# 08_FPGA_banks_1_2_3_4.net
KiCad netlist of a schematic drawn in Altium Designer
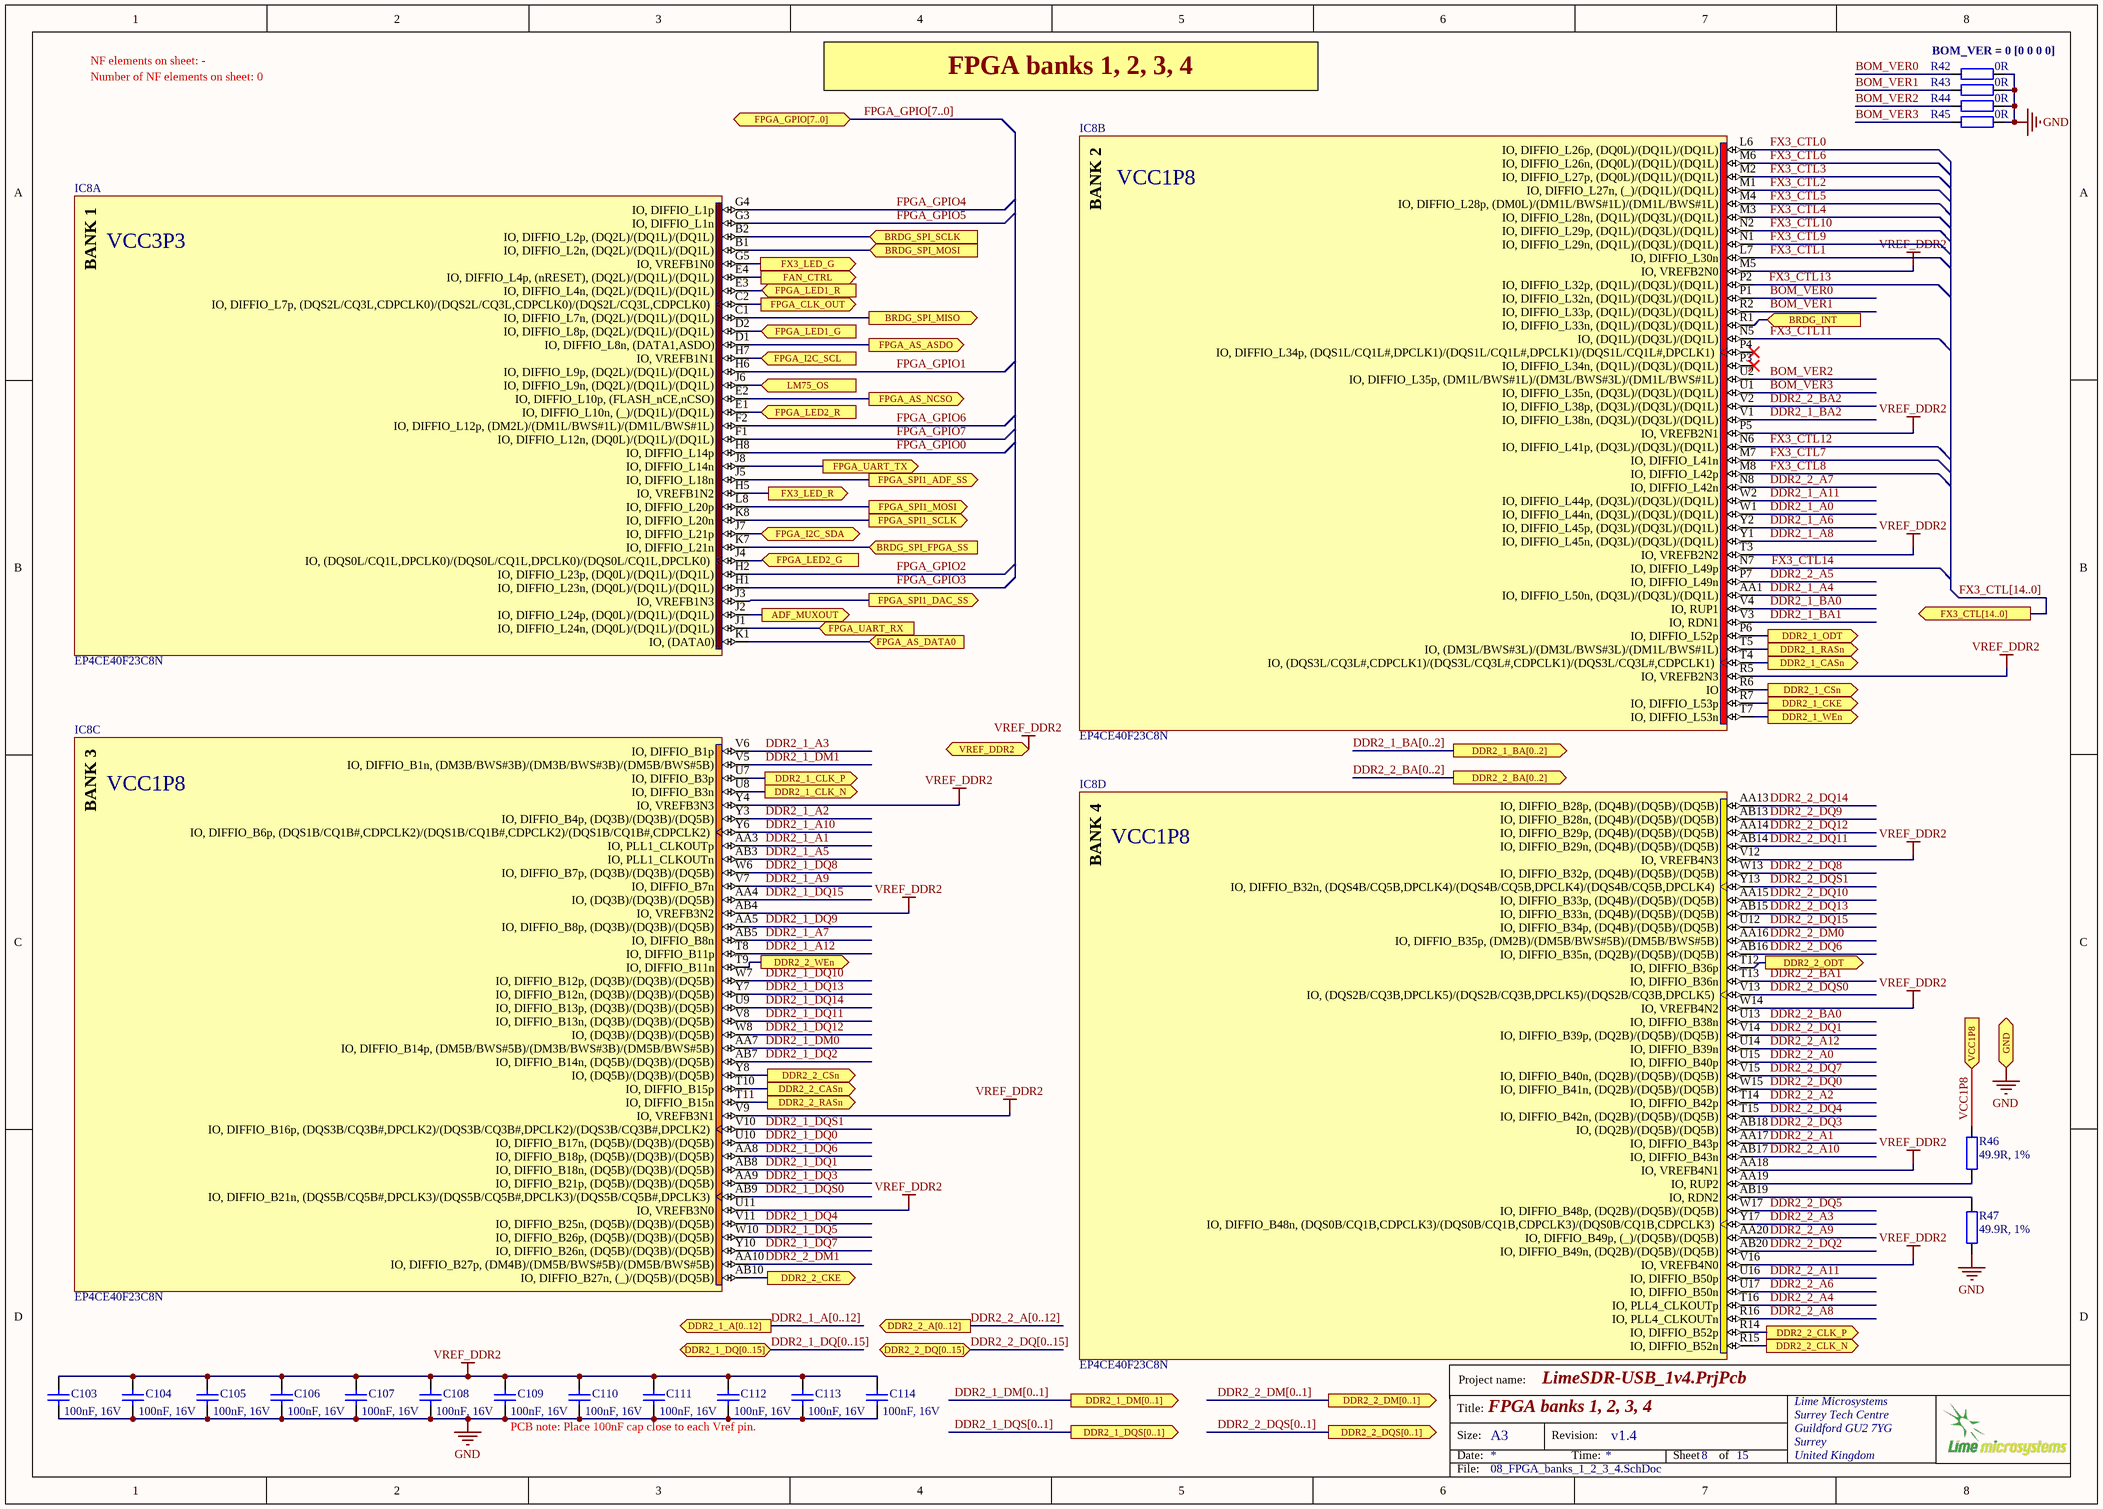
[diagram p0: 08_FPGA_banks_1_2_3_4.SchDoc]

(export (version "E")
  (design (tool "Eeschema 10.0.6"))
  (components
    (comp (ref "C103")
      (value "100nF, 16V")
      (footprint "CAP0402")
      (fields
        (field (name "TOLERANCE") "10 %")
        (field (name "MANUFACTURER") "Murata Electronics")
        (field (name "MANUFACTURER PART NUMBER") "GRM155R71C104KA88D")
      )
      (libsource (lib "LimeFPGAboard_schLib") (part "Cap_0603"))
    )
    (comp (ref "C104")
      (value "100nF, 16V")
      (footprint "CAP0402")
      (fields
        (field (name "TOLERANCE") "10 %")
        (field (name "MANUFACTURER") "Murata Electronics")
        (field (name "MANUFACTURER PART NUMBER") "GRM155R71C104KA88D")
      )
      (libsource (lib "LimeFPGAboard_schLib") (part "Cap_0603"))
    )
    (comp (ref "C105")
      (value "100nF, 16V")
      (footprint "CAP0402")
      (fields
        (field (name "TOLERANCE") "10 %")
        (field (name "MANUFACTURER") "Murata Electronics")
        (field (name "MANUFACTURER PART NUMBER") "GRM155R71C104KA88D")
      )
      (libsource (lib "LimeFPGAboard_schLib") (part "Cap_0603"))
    )
    (comp (ref "C106")
      (value "100nF, 16V")
      (footprint "CAP0402")
      (fields
        (field (name "TOLERANCE") "10 %")
        (field (name "MANUFACTURER") "Murata Electronics")
        (field (name "MANUFACTURER PART NUMBER") "GRM155R71C104KA88D")
      )
      (libsource (lib "LimeFPGAboard_schLib") (part "Cap_0603"))
    )
    (comp (ref "C107")
      (value "100nF, 16V")
      (footprint "CAP0402")
      (fields
        (field (name "TOLERANCE") "10 %")
        (field (name "MANUFACTURER") "Murata Electronics")
        (field (name "MANUFACTURER PART NUMBER") "GRM155R71C104KA88D")
      )
      (libsource (lib "LimeFPGAboard_schLib") (part "Cap_0603"))
    )
    (comp (ref "C108")
      (value "100nF, 16V")
      (footprint "CAP0402")
      (fields
        (field (name "TOLERANCE") "10 %")
        (field (name "MANUFACTURER") "Murata Electronics")
        (field (name "MANUFACTURER PART NUMBER") "GRM155R71C104KA88D")
      )
      (libsource (lib "LimeFPGAboard_schLib") (part "Cap_0603"))
    )
    (comp (ref "C109")
      (value "100nF, 16V")
      (footprint "CAP0402")
      (fields
        (field (name "TOLERANCE") "10 %")
        (field (name "MANUFACTURER") "Murata Electronics")
        (field (name "MANUFACTURER PART NUMBER") "GRM155R71C104KA88D")
      )
      (libsource (lib "LimeFPGAboard_schLib") (part "Cap_0603"))
    )
    (comp (ref "C110")
      (value "100nF, 16V")
      (footprint "CAP0402")
      (fields
        (field (name "TOLERANCE") "10 %")
        (field (name "MANUFACTURER") "Murata Electronics")
        (field (name "MANUFACTURER PART NUMBER") "GRM155R71C104KA88D")
      )
      (libsource (lib "LimeFPGAboard_schLib") (part "Cap_0603"))
    )
    (comp (ref "C111")
      (value "100nF, 16V")
      (footprint "CAP0402")
      (fields
        (field (name "TOLERANCE") "10 %")
        (field (name "MANUFACTURER") "Murata Electronics")
        (field (name "MANUFACTURER PART NUMBER") "GRM155R71C104KA88D")
      )
      (libsource (lib "LimeFPGAboard_schLib") (part "Cap_0603"))
    )
    (comp (ref "C112")
      (value "100nF, 16V")
      (footprint "CAP0402")
      (fields
        (field (name "TOLERANCE") "10 %")
        (field (name "MANUFACTURER") "Murata Electronics")
        (field (name "MANUFACTURER PART NUMBER") "GRM155R71C104KA88D")
      )
      (libsource (lib "LimeFPGAboard_schLib") (part "Cap_0603"))
    )
    (comp (ref "C113")
      (value "100nF, 16V")
      (footprint "CAP0402")
      (fields
        (field (name "TOLERANCE") "10 %")
        (field (name "MANUFACTURER") "Murata Electronics")
        (field (name "MANUFACTURER PART NUMBER") "GRM155R71C104KA88D")
      )
      (libsource (lib "LimeFPGAboard_schLib") (part "Cap_0603"))
    )
    (comp (ref "C114")
      (value "100nF, 16V")
      (footprint "CAP0402")
      (fields
        (field (name "TOLERANCE") "10 %")
        (field (name "MANUFACTURER") "Murata Electronics")
        (field (name "MANUFACTURER PART NUMBER") "GRM155R71C104KA88D")
      )
      (libsource (lib "LimeFPGAboard_schLib") (part "Cap_0603"))
    )
    (comp (ref "IC8")
      (value "EP4CE40F23C8N")
      (footprint "FBGA484_A-240")
      (description "IC FPGA 328 I/O 484FBGA")
      (fields (field (name "MANUFACTURER") "Altera"))
      (libsource (lib "LimeMicroAltiumLib_schLib") (part "EP4CE40F23C7N"))
    )
    (comp (ref "R42")
      (value "0R")
      (footprint "RES0402")
      (fields (field (name "MANUFACTURER") "Yageo"))
      (libsource (lib "LimeFPGAboard_schLib") (part "Res_0402"))
    )
    (comp (ref "R43")
      (value "0R")
      (footprint "RES0402")
      (fields (field (name "MANUFACTURER") "Yageo"))
      (libsource (lib "LimeFPGAboard_schLib") (part "Res_0402"))
    )
    (comp (ref "R44")
      (value "0R")
      (footprint "RES0402")
      (fields (field (name "MANUFACTURER") "Yageo"))
      (libsource (lib "LimeFPGAboard_schLib") (part "Res_0402"))
    )
    (comp (ref "R45")
      (value "0R")
      (footprint "RES0402")
      (fields (field (name "MANUFACTURER") "Yageo"))
      (libsource (lib "LimeFPGAboard_schLib") (part "Res_0402"))
    )
    (comp (ref "R46")
      (value "49.9R, 1%")
      (footprint "RES0402")
      (fields
        (field (name "TOLERANCE") "±1%")
        (field (name "MANUFACTURER") "Samsung Electro-Mechanics America, Inc.")
        (field (name "MANUFACTURER PART NUMBER") "RC1005F49R9CS")
      )
      (libsource (lib "LimeMicroAltiumLib_schLib") (part "Res_0402"))
    )
    (comp (ref "R47")
      (value "49.9R, 1%")
      (footprint "RES0402")
      (fields
        (field (name "TOLERANCE") "±1%")
        (field (name "MANUFACTURER") "Samsung Electro-Mechanics America, Inc.")
        (field (name "MANUFACTURER PART NUMBER") "RC1005F49R9CS")
      )
      (libsource (lib "LimeMicroAltiumLib_schLib") (part "Res_0402"))
    )
  )
  (nets
    (net (code "1") (name "/ADF_MUXOUT") (class "Default")
      (node (ref "IC8") (pin "J2") (pinfunction "IO,_DIFFIO_L24p,_(DQ0L)/(DQ1L)/(DQ1L)_J2") (pintype "bidirectional"))
    )
    (net (code "2") (name "/BOM_VER0") (class "Default")
      (node (ref "IC8") (pin "P1") (pinfunction "IO,_DIFFIO_L32n,_(DQ1L)/(DQ3L)/(DQ1L)_P1") (pintype "bidirectional"))
      (node (ref "R42") (pin "1") (pinfunction "1_1") (pintype "passive"))
    )
    (net (code "3") (name "/BOM_VER1") (class "Default")
      (node (ref "IC8") (pin "R2") (pinfunction "IO,_DIFFIO_L33p,_(DQ1L)/(DQ3L)/(DQ1L)_R2") (pintype "bidirectional"))
      (node (ref "R43") (pin "1") (pinfunction "1_1") (pintype "passive"))
    )
    (net (code "4") (name "/BOM_VER2") (class "Default")
      (node (ref "IC8") (pin "U2") (pinfunction "IO,_DIFFIO_L35p,_(DM1L/BWS#1L)/(DM3L/BWS#3L)/(DM1L/BWS#1L)_U2") (pintype "bidirectional"))
      (node (ref "R44") (pin "1") (pinfunction "1_1") (pintype "passive"))
    )
    (net (code "5") (name "/BOM_VER3") (class "Default")
      (node (ref "IC8") (pin "U1") (pinfunction "IO,_DIFFIO_L35n,_(DQ3L)/(DQ3L)/(DQ1L)_U1") (pintype "bidirectional"))
      (node (ref "R45") (pin "1") (pinfunction "1_1") (pintype "passive"))
    )
    (net (code "6") (name "/BRDG_INT") (class "Default")
      (node (ref "IC8") (pin "R1") (pinfunction "IO,_DIFFIO_L33n,_(DQ1L)/(DQ3L)/(DQ1L)_R1") (pintype "bidirectional"))
    )
    (net (code "7") (name "/BRDG_SPI_FPGA_SS") (class "Default")
      (node (ref "IC8") (pin "K7") (pinfunction "IO,_DIFFIO_L21n_K7") (pintype "bidirectional"))
    )
    (net (code "8") (name "/BRDG_SPI_MISO") (class "Default")
      (node (ref "IC8") (pin "C1") (pinfunction "IO,_DIFFIO_L7n,_(DQ2L)/(DQ1L)/(DQ1L)_C1") (pintype "bidirectional"))
    )
    (net (code "9") (name "/BRDG_SPI_MOSI") (class "Default")
      (node (ref "IC8") (pin "B1") (pinfunction "IO,_DIFFIO_L2n,_(DQ2L)/(DQ1L)/(DQ1L)_B1") (pintype "bidirectional"))
    )
    (net (code "10") (name "/BRDG_SPI_SCLK") (class "Default")
      (node (ref "IC8") (pin "B2") (pinfunction "IO,_DIFFIO_L2p,_(DQ2L)/(DQ1L)/(DQ1L)_B2") (pintype "bidirectional"))
    )
    (net (code "11") (name "/DDR2_1_A0") (class "Default")
      (node (ref "IC8") (pin "W1") (pinfunction "IO,_DIFFIO_L44n,_(DQ3L)/(DQ3L)/(DQ1L)_W1") (pintype "bidirectional"))
    )
    (net (code "12") (name "/DDR2_1_A1") (class "Default")
      (node (ref "IC8") (pin "AA3") (pinfunction "IO,_PLL1_CLKOUTp_AA3") (pintype "bidirectional"))
    )
    (net (code "13") (name "/DDR2_1_A2") (class "Default")
      (node (ref "IC8") (pin "Y3") (pinfunction "IO,_DIFFIO_B4p,_(DQ3B)/(DQ3B)/(DQ5B)_Y3") (pintype "bidirectional"))
    )
    (net (code "14") (name "/DDR2_1_A3") (class "Default")
      (node (ref "IC8") (pin "V6") (pinfunction "IO,_DIFFIO_B1p_V6") (pintype "bidirectional"))
    )
    (net (code "15") (name "/DDR2_1_A4") (class "Default")
      (node (ref "IC8") (pin "AA1") (pinfunction "IO,_DIFFIO_L50n,_(DQ3L)/(DQ3L)/(DQ1L)_AA1") (pintype "bidirectional"))
    )
    (net (code "16") (name "/DDR2_1_A5") (class "Default")
      (node (ref "IC8") (pin "AB3") (pinfunction "IO,_PLL1_CLKOUTn_AB3") (pintype "bidirectional"))
    )
    (net (code "17") (name "/DDR2_1_A6") (class "Default")
      (node (ref "IC8") (pin "Y2") (pinfunction "IO,_DIFFIO_L45p,_(DQ3L)/(DQ3L)/(DQ1L)_Y2") (pintype "bidirectional"))
    )
    (net (code "18") (name "/DDR2_1_A7") (class "Default")
      (node (ref "IC8") (pin "AB5") (pinfunction "IO,_DIFFIO_B8n_AB5") (pintype "bidirectional"))
    )
    (net (code "19") (name "/DDR2_1_A8") (class "Default")
      (node (ref "IC8") (pin "Y1") (pinfunction "IO,_DIFFIO_L45n,_(DQ3L)/(DQ3L)/(DQ1L)_Y1") (pintype "bidirectional"))
    )
    (net (code "20") (name "/DDR2_1_A9") (class "Default")
      (node (ref "IC8") (pin "V7") (pinfunction "IO,_DIFFIO_B7n_V7") (pintype "bidirectional"))
    )
    (net (code "21") (name "/DDR2_1_A10") (class "Default")
      (node (ref "IC8") (pin "Y6") (pinfunction "IO,_DIFFIO_B6p,_(DQS1B/CQ1B#,CDPCLK2)/(DQS1B/CQ1B#,CDPCLK2)/(DQS1B/CQ1B#,CDPCLK2)_Y6") (pintype "bidirectional"))
    )
    (net (code "22") (name "/DDR2_1_A11") (class "Default")
      (node (ref "IC8") (pin "W2") (pinfunction "IO,_DIFFIO_L44p,_(DQ3L)/(DQ3L)/(DQ1L)_W2") (pintype "bidirectional"))
    )
    (net (code "23") (name "/DDR2_1_A12") (class "Default")
      (node (ref "IC8") (pin "T8") (pinfunction "IO,_DIFFIO_B11p_T8") (pintype "bidirectional"))
    )
    (net (code "25") (name "/DDR2_1_BA0") (class "Default")
      (node (ref "IC8") (pin "V4") (pinfunction "IO,_RUP1_V4") (pintype "bidirectional"))
    )
    (net (code "26") (name "/DDR2_1_BA1") (class "Default")
      (node (ref "IC8") (pin "V3") (pinfunction "IO,_RDN1_V3") (pintype "bidirectional"))
    )
    (net (code "27") (name "/DDR2_1_BA2") (class "Default")
      (node (ref "IC8") (pin "V1") (pinfunction "IO,_DIFFIO_L38n,_(DQ3L)/(DQ3L)/(DQ1L)_V1") (pintype "bidirectional"))
    )
    (net (code "29") (name "/DDR2_1_CASn") (class "Default")
      (node (ref "IC8") (pin "T4") (pinfunction "IO,_(DQS3L/CQ3L#,CDPCLK1)/(DQS3L/CQ3L#,CDPCLK1)/(DQS3L/CQ3L#,CDPCLK1)_T4") (pintype "bidirectional"))
    )
    (net (code "30") (name "/DDR2_1_CKE") (class "Default")
      (node (ref "IC8") (pin "R7") (pinfunction "IO,_DIFFIO_L53p_R7") (pintype "bidirectional"))
    )
    (net (code "31") (name "/DDR2_1_CLK_N") (class "Default")
      (node (ref "IC8") (pin "U8") (pinfunction "IO,_DIFFIO_B3n_U8") (pintype "bidirectional"))
    )
    (net (code "32") (name "/DDR2_1_CLK_P") (class "Default")
      (node (ref "IC8") (pin "U7") (pinfunction "IO,_DIFFIO_B3p_U7") (pintype "bidirectional"))
    )
    (net (code "33") (name "/DDR2_1_CSn") (class "Default")
      (node (ref "IC8") (pin "R6") (pinfunction "IO_R6") (pintype "bidirectional"))
    )
    (net (code "34") (name "/DDR2_1_DM0") (class "Default")
      (node (ref "IC8") (pin "AA7") (pinfunction "IO,_DIFFIO_B14p,_(DM5B/BWS#5B)/(DM3B/BWS#3B)/(DM5B/BWS#5B)_AA7") (pintype "bidirectional"))
    )
    (net (code "35") (name "/DDR2_1_DM1") (class "Default")
      (node (ref "IC8") (pin "V5") (pinfunction "IO,_DIFFIO_B1n,_(DM3B/BWS#3B)/(DM3B/BWS#3B)/(DM5B/BWS#5B)_V5") (pintype "bidirectional"))
    )
    (net (code "37") (name "/DDR2_1_DQ0") (class "Default")
      (node (ref "IC8") (pin "U10") (pinfunction "IO,_DIFFIO_B17n,_(DQ5B)/(DQ3B)/(DQ5B)_U10") (pintype "bidirectional"))
    )
    (net (code "38") (name "/DDR2_1_DQ1") (class "Default")
      (node (ref "IC8") (pin "AB8") (pinfunction "IO,_DIFFIO_B18n,_(DQ5B)/(DQ3B)/(DQ5B)_AB8") (pintype "bidirectional"))
    )
    (net (code "39") (name "/DDR2_1_DQ2") (class "Default")
      (node (ref "IC8") (pin "AB7") (pinfunction "IO,_DIFFIO_B14n,_(DQ5B)/(DQ3B)/(DQ5B)_AB7") (pintype "bidirectional"))
    )
    (net (code "40") (name "/DDR2_1_DQ3") (class "Default")
      (node (ref "IC8") (pin "AA9") (pinfunction "IO,_DIFFIO_B21p,_(DQ5B)/(DQ3B)/(DQ5B)_AA9") (pintype "bidirectional"))
    )
    (net (code "41") (name "/DDR2_1_DQ4") (class "Default")
      (node (ref "IC8") (pin "V11") (pinfunction "IO,_DIFFIO_B25n,_(DQ5B)/(DQ3B)/(DQ5B)_V11") (pintype "bidirectional"))
    )
    (net (code "42") (name "/DDR2_1_DQ5") (class "Default")
      (node (ref "IC8") (pin "W10") (pinfunction "IO,_DIFFIO_B26p,_(DQ5B)/(DQ3B)/(DQ5B)_W10") (pintype "bidirectional"))
    )
    (net (code "43") (name "/DDR2_1_DQ6") (class "Default")
      (node (ref "IC8") (pin "AA8") (pinfunction "IO,_DIFFIO_B18p,_(DQ5B)/(DQ3B)/(DQ5B)_AA8") (pintype "bidirectional"))
    )
    (net (code "44") (name "/DDR2_1_DQ7") (class "Default")
      (node (ref "IC8") (pin "Y10") (pinfunction "IO,_DIFFIO_B26n,_(DQ5B)/(DQ3B)/(DQ5B)_Y10") (pintype "bidirectional"))
    )
    (net (code "45") (name "/DDR2_1_DQ8") (class "Default")
      (node (ref "IC8") (pin "W6") (pinfunction "IO,_DIFFIO_B7p,_(DQ3B)/(DQ3B)/(DQ5B)_W6") (pintype "bidirectional"))
    )
    (net (code "46") (name "/DDR2_1_DQ9") (class "Default")
      (node (ref "IC8") (pin "AA5") (pinfunction "IO,_DIFFIO_B8p,_(DQ3B)/(DQ3B)/(DQ5B)_AA5") (pintype "bidirectional"))
    )
    (net (code "47") (name "/DDR2_1_DQ10") (class "Default")
      (node (ref "IC8") (pin "W7") (pinfunction "IO,_DIFFIO_B12p,_(DQ3B)/(DQ3B)/(DQ5B)_W7") (pintype "bidirectional"))
    )
    (net (code "48") (name "/DDR2_1_DQ11") (class "Default")
      (node (ref "IC8") (pin "V8") (pinfunction "IO,_DIFFIO_B13n,_(DQ3B)/(DQ3B)/(DQ5B)_V8") (pintype "bidirectional"))
    )
    (net (code "49") (name "/DDR2_1_DQ12") (class "Default")
      (node (ref "IC8") (pin "W8") (pinfunction "IO,_(DQ3B)/(DQ3B)/(DQ5B)_W8") (pintype "bidirectional"))
    )
    (net (code "50") (name "/DDR2_1_DQ13") (class "Default")
      (node (ref "IC8") (pin "Y7") (pinfunction "IO,_DIFFIO_B12n,_(DQ3B)/(DQ3B)/(DQ5B)_Y7") (pintype "bidirectional"))
    )
    (net (code "51") (name "/DDR2_1_DQ14") (class "Default")
      (node (ref "IC8") (pin "U9") (pinfunction "IO,_DIFFIO_B13p,_(DQ3B)/(DQ3B)/(DQ5B)_U9") (pintype "bidirectional"))
    )
    (net (code "52") (name "/DDR2_1_DQ15") (class "Default")
      (node (ref "IC8") (pin "AA4") (pinfunction "IO,_(DQ3B)/(DQ3B)/(DQ5B)_AA4") (pintype "bidirectional"))
    )
    (net (code "53") (name "/DDR2_1_DQS0") (class "Default")
      (node (ref "IC8") (pin "AB9") (pinfunction "IO,_DIFFIO_B21n,_(DQS5B/CQ5B#,DPCLK3)/(DQS5B/CQ5B#,DPCLK3)/(DQS5B/CQ5B#,DPCLK3)_AB9") (pintype "bidirectional"))
    )
    (net (code "54") (name "/DDR2_1_DQS1") (class "Default")
      (node (ref "IC8") (pin "V10") (pinfunction "IO,_DIFFIO_B16p,_(DQS3B/CQ3B#,DPCLK2)/(DQS3B/CQ3B#,DPCLK2)/(DQS3B/CQ3B#,DPCLK2)_V10") (pintype "bidirectional"))
    )
    (net (code "57") (name "/DDR2_1_ODT") (class "Default")
      (node (ref "IC8") (pin "P6") (pinfunction "IO,_DIFFIO_L52p_P6") (pintype "bidirectional"))
    )
    (net (code "58") (name "/DDR2_1_RASn") (class "Default")
      (node (ref "IC8") (pin "T5") (pinfunction "IO,_(DM3L/BWS#3L)/(DM3L/BWS#3L)/(DM1L/BWS#1L)_T5") (pintype "bidirectional"))
    )
    (net (code "59") (name "/DDR2_1_WEn") (class "Default")
      (node (ref "IC8") (pin "T7") (pinfunction "IO,_DIFFIO_L53n_T7") (pintype "bidirectional"))
    )
    (net (code "60") (name "/DDR2_2_A0") (class "Default")
      (node (ref "IC8") (pin "U15") (pinfunction "IO,_DIFFIO_B40p_U15") (pintype "bidirectional"))
    )
    (net (code "61") (name "/DDR2_2_A1") (class "Default")
      (node (ref "IC8") (pin "AA17") (pinfunction "IO,_DIFFIO_B43p_AA17") (pintype "bidirectional"))
    )
    (net (code "62") (name "/DDR2_2_A2") (class "Default")
      (node (ref "IC8") (pin "T14") (pinfunction "IO,_DIFFIO_B42p_T14") (pintype "bidirectional"))
    )
    (net (code "63") (name "/DDR2_2_A3") (class "Default")
      (node (ref "IC8") (pin "Y17") (pinfunction "IO,_DIFFIO_B48n,_(DQS0B/CQ1B,CDPCLK3)/(DQS0B/CQ1B,CDPCLK3)/(DQS0B/CQ1B,CDPCLK3)_Y17") (pintype "bidirectional"))
    )
    (net (code "64") (name "/DDR2_2_A4") (class "Default")
      (node (ref "IC8") (pin "T16") (pinfunction "IO,_PLL4_CLKOUTp_T16") (pintype "bidirectional"))
    )
    (net (code "65") (name "/DDR2_2_A5") (class "Default")
      (node (ref "IC8") (pin "P7") (pinfunction "IO,_DIFFIO_L49n_P7") (pintype "bidirectional"))
    )
    (net (code "66") (name "/DDR2_2_A6") (class "Default")
      (node (ref "IC8") (pin "U17") (pinfunction "IO,_DIFFIO_B50n_U17") (pintype "bidirectional"))
    )
    (net (code "67") (name "/DDR2_2_A7") (class "Default")
      (node (ref "IC8") (pin "N8") (pinfunction "IO,_DIFFIO_L42n_N8") (pintype "bidirectional"))
    )
    (net (code "68") (name "/DDR2_2_A8") (class "Default")
      (node (ref "IC8") (pin "R16") (pinfunction "IO,_PLL4_CLKOUTn_R16") (pintype "bidirectional"))
    )
    (net (code "69") (name "/DDR2_2_A9") (class "Default")
      (node (ref "IC8") (pin "AA20") (pinfunction "IO,_DIFFIO_B49p,_(_)/(DQ5B)/(DQ5B)_AA20") (pintype "bidirectional"))
    )
    (net (code "70") (name "/DDR2_2_A10") (class "Default")
      (node (ref "IC8") (pin "AB17") (pinfunction "IO,_DIFFIO_B43n_AB17") (pintype "bidirectional"))
    )
    (net (code "71") (name "/DDR2_2_A11") (class "Default")
      (node (ref "IC8") (pin "U16") (pinfunction "IO,_DIFFIO_B50p_U16") (pintype "bidirectional"))
    )
    (net (code "72") (name "/DDR2_2_A12") (class "Default")
      (node (ref "IC8") (pin "U14") (pinfunction "IO,_DIFFIO_B39n_U14") (pintype "bidirectional"))
    )
    (net (code "74") (name "/DDR2_2_BA0") (class "Default")
      (node (ref "IC8") (pin "U13") (pinfunction "IO,_DIFFIO_B38n_U13") (pintype "bidirectional"))
    )
    (net (code "75") (name "/DDR2_2_BA1") (class "Default")
      (node (ref "IC8") (pin "T13") (pinfunction "IO,_DIFFIO_B36n_T13") (pintype "bidirectional"))
    )
    (net (code "76") (name "/DDR2_2_BA2") (class "Default")
      (node (ref "IC8") (pin "V2") (pinfunction "IO,_DIFFIO_L38p,_(DQ3L)/(DQ3L)/(DQ1L)_V2") (pintype "bidirectional"))
    )
    (net (code "78") (name "/DDR2_2_CASn") (class "Default")
      (node (ref "IC8") (pin "T10") (pinfunction "IO,_DIFFIO_B15p_T10") (pintype "bidirectional"))
    )
    (net (code "79") (name "/DDR2_2_CKE") (class "Default")
      (node (ref "IC8") (pin "AB10") (pinfunction "IO,_DIFFIO_B27n,_(_)/(DQ5B)/(DQ5B)_AB10") (pintype "bidirectional"))
    )
    (net (code "80") (name "/DDR2_2_CLK_N") (class "Default")
      (node (ref "IC8") (pin "R15") (pinfunction "IO,_DIFFIO_B52n_R15") (pintype "bidirectional"))
    )
    (net (code "81") (name "/DDR2_2_CLK_P") (class "Default")
      (node (ref "IC8") (pin "R14") (pinfunction "IO,_DIFFIO_B52p_R14") (pintype "bidirectional"))
    )
    (net (code "82") (name "/DDR2_2_CSn") (class "Default")
      (node (ref "IC8") (pin "Y8") (pinfunction "IO,_(DQ5B)/(DQ3B)/(DQ5B)_Y8") (pintype "bidirectional"))
    )
    (net (code "83") (name "/DDR2_2_DM0") (class "Default")
      (node (ref "IC8") (pin "AA16") (pinfunction "IO,_DIFFIO_B35p,_(DM2B)/(DM5B/BWS#5B)/(DM5B/BWS#5B)_AA16") (pintype "bidirectional"))
    )
    (net (code "84") (name "/DDR2_2_DM1") (class "Default")
      (node (ref "IC8") (pin "AA10") (pinfunction "IO,_DIFFIO_B27p,_(DM4B)/(DM5B/BWS#5B)/(DM5B/BWS#5B)_AA10") (pintype "bidirectional"))
    )
    (net (code "86") (name "/DDR2_2_DQ0") (class "Default")
      (node (ref "IC8") (pin "W15") (pinfunction "IO,_DIFFIO_B41n,_(DQ2B)/(DQ5B)/(DQ5B)_W15") (pintype "bidirectional"))
    )
    (net (code "87") (name "/DDR2_2_DQ1") (class "Default")
      (node (ref "IC8") (pin "V14") (pinfunction "IO,_DIFFIO_B39p,_(DQ2B)/(DQ5B)/(DQ5B)_V14") (pintype "bidirectional"))
    )
    (net (code "88") (name "/DDR2_2_DQ2") (class "Default")
      (node (ref "IC8") (pin "AB20") (pinfunction "IO,_DIFFIO_B49n,_(DQ2B)/(DQ5B)/(DQ5B)_AB20") (pintype "bidirectional"))
    )
    (net (code "89") (name "/DDR2_2_DQ3") (class "Default")
      (node (ref "IC8") (pin "AB18") (pinfunction "IO,_(DQ2B)/(DQ5B)/(DQ5B)_AB18") (pintype "bidirectional"))
    )
    (net (code "90") (name "/DDR2_2_DQ4") (class "Default")
      (node (ref "IC8") (pin "T15") (pinfunction "IO,_DIFFIO_B42n,_(DQ2B)/(DQ5B)/(DQ5B)_T15") (pintype "bidirectional"))
    )
    (net (code "91") (name "/DDR2_2_DQ5") (class "Default")
      (node (ref "IC8") (pin "W17") (pinfunction "IO,_DIFFIO_B48p,_(DQ2B)/(DQ5B)/(DQ5B)_W17") (pintype "bidirectional"))
    )
    (net (code "92") (name "/DDR2_2_DQ6") (class "Default")
      (node (ref "IC8") (pin "AB16") (pinfunction "IO,_DIFFIO_B35n,_(DQ2B)/(DQ5B)/(DQ5B)_AB16") (pintype "bidirectional"))
    )
    (net (code "93") (name "/DDR2_2_DQ7") (class "Default")
      (node (ref "IC8") (pin "V15") (pinfunction "IO,_DIFFIO_B40n,_(DQ2B)/(DQ5B)/(DQ5B)_V15") (pintype "bidirectional"))
    )
    (net (code "94") (name "/DDR2_2_DQ8") (class "Default")
      (node (ref "IC8") (pin "W13") (pinfunction "IO,_DIFFIO_B32p,_(DQ4B)/(DQ5B)/(DQ5B)_W13") (pintype "bidirectional"))
    )
    (net (code "95") (name "/DDR2_2_DQ9") (class "Default")
      (node (ref "IC8") (pin "AB13") (pinfunction "IO,_DIFFIO_B28n,_(DQ4B)/(DQ5B)/(DQ5B)_AB13") (pintype "bidirectional"))
    )
    (net (code "96") (name "/DDR2_2_DQ10") (class "Default")
      (node (ref "IC8") (pin "AA15") (pinfunction "IO,_DIFFIO_B33p,_(DQ4B)/(DQ5B)/(DQ5B)_AA15") (pintype "bidirectional"))
    )
    (net (code "97") (name "/DDR2_2_DQ11") (class "Default")
      (node (ref "IC8") (pin "AB14") (pinfunction "IO,_DIFFIO_B29n,_(DQ4B)/(DQ5B)/(DQ5B)_AB14") (pintype "bidirectional"))
    )
    (net (code "98") (name "/DDR2_2_DQ12") (class "Default")
      (node (ref "IC8") (pin "AA14") (pinfunction "IO,_DIFFIO_B29p,_(DQ4B)/(DQ5B)/(DQ5B)_AA14") (pintype "bidirectional"))
    )
    (net (code "99") (name "/DDR2_2_DQ13") (class "Default")
      (node (ref "IC8") (pin "AB15") (pinfunction "IO,_DIFFIO_B33n,_(DQ4B)/(DQ5B)/(DQ5B)_AB15") (pintype "bidirectional"))
    )
    (net (code "100") (name "/DDR2_2_DQ14") (class "Default")
      (node (ref "IC8") (pin "AA13") (pinfunction "IO,_DIFFIO_B28p,_(DQ4B)/(DQ5B)/(DQ5B)_AA13") (pintype "bidirectional"))
    )
    (net (code "101") (name "/DDR2_2_DQ15") (class "Default")
      (node (ref "IC8") (pin "U12") (pinfunction "IO,_DIFFIO_B34p,_(DQ4B)/(DQ5B)/(DQ5B)_U12") (pintype "bidirectional"))
    )
    (net (code "102") (name "/DDR2_2_DQS0") (class "Default")
      (node (ref "IC8") (pin "V13") (pinfunction "IO,_(DQS2B/CQ3B,DPCLK5)/(DQS2B/CQ3B,DPCLK5)/(DQS2B/CQ3B,DPCLK5)_V13") (pintype "bidirectional"))
    )
    (net (code "103") (name "/DDR2_2_DQS1") (class "Default")
      (node (ref "IC8") (pin "Y13") (pinfunction "IO,_DIFFIO_B32n,_(DQS4B/CQ5B,DPCLK4)/(DQS4B/CQ5B,DPCLK4)/(DQS4B/CQ5B,DPCLK4)_Y13") (pintype "bidirectional"))
    )
    (net (code "106") (name "/DDR2_2_ODT") (class "Default")
      (node (ref "IC8") (pin "T12") (pinfunction "IO,_DIFFIO_B36p_T12") (pintype "bidirectional"))
    )
    (net (code "107") (name "/DDR2_2_RASn") (class "Default")
      (node (ref "IC8") (pin "T11") (pinfunction "IO,_DIFFIO_B15n_T11") (pintype "bidirectional"))
    )
    (net (code "108") (name "/DDR2_2_WEn") (class "Default")
      (node (ref "IC8") (pin "T9") (pinfunction "IO,_DIFFIO_B11n_T9") (pintype "bidirectional"))
    )
    (net (code "109") (name "/FAN_CTRL") (class "Default")
      (node (ref "IC8") (pin "E4") (pinfunction "IO,_DIFFIO_L4p,_(nRESET),_(DQ2L)/(DQ1L)/(DQ1L)_E4") (pintype "bidirectional"))
    )
    (net (code "110") (name "/FPGA_AS_ASDO") (class "Default")
      (node (ref "IC8") (pin "D1") (pinfunction "IO,_DIFFIO_L8n,_(DATA1,ASDO)_D1") (pintype "bidirectional"))
    )
    (net (code "111") (name "/FPGA_AS_DATA0") (class "Default")
      (node (ref "IC8") (pin "K1") (pinfunction "IO,_(DATA0)_K1") (pintype "bidirectional"))
    )
    (net (code "112") (name "/FPGA_AS_NCSO") (class "Default")
      (node (ref "IC8") (pin "E2") (pinfunction "IO,_DIFFIO_L10p,_(FLASH_nCE,nCSO)_E2") (pintype "bidirectional"))
    )
    (net (code "113") (name "/FPGA_CLK_OUT") (class "Default")
      (node (ref "IC8") (pin "C2") (pinfunction "IO,_DIFFIO_L7p,_(DQS2L/CQ3L,CDPCLK0)/(DQS2L/CQ3L,CDPCLK0)/(DQS2L/CQ3L,CDPCLK0)_C2") (pintype "bidirectional"))
    )
    (net (code "114") (name "/FPGA_GPIO0") (class "Default")
      (node (ref "IC8") (pin "H8") (pinfunction "IO,_DIFFIO_L14p_H8") (pintype "bidirectional"))
    )
    (net (code "115") (name "/FPGA_GPIO1") (class "Default")
      (node (ref "IC8") (pin "H6") (pinfunction "IO,_DIFFIO_L9p,_(DQ2L)/(DQ1L)/(DQ1L)_H6") (pintype "bidirectional"))
    )
    (net (code "116") (name "/FPGA_GPIO2") (class "Default")
      (node (ref "IC8") (pin "H2") (pinfunction "IO,_DIFFIO_L23p,_(DQ0L)/(DQ1L)/(DQ1L)_H2") (pintype "bidirectional"))
    )
    (net (code "117") (name "/FPGA_GPIO3") (class "Default")
      (node (ref "IC8") (pin "H1") (pinfunction "IO,_DIFFIO_L23n,_(DQ0L)/(DQ1L)/(DQ1L)_H1") (pintype "bidirectional"))
    )
    (net (code "118") (name "/FPGA_GPIO4") (class "Default")
      (node (ref "IC8") (pin "G4") (pinfunction "IO,_DIFFIO_L1p_G4") (pintype "bidirectional"))
    )
    (net (code "119") (name "/FPGA_GPIO5") (class "Default")
      (node (ref "IC8") (pin "G3") (pinfunction "IO,_DIFFIO_L1n_G3") (pintype "bidirectional"))
    )
    (net (code "120") (name "/FPGA_GPIO6") (class "Default")
      (node (ref "IC8") (pin "F2") (pinfunction "IO,_DIFFIO_L12p,_(DM2L)/(DM1L/BWS#1L)/(DM1L/BWS#1L)_F2") (pintype "bidirectional"))
    )
    (net (code "121") (name "/FPGA_GPIO7") (class "Default")
      (node (ref "IC8") (pin "F1") (pinfunction "IO,_DIFFIO_L12n,_(DQ0L)/(DQ1L)/(DQ1L)_F1") (pintype "bidirectional"))
    )
    (net (code "123") (name "/FPGA_I2C_SCL") (class "Default")
      (node (ref "IC8") (pin "H7") (pinfunction "IO,_VREFB1N1_H7") (pintype "bidirectional"))
    )
    (net (code "124") (name "/FPGA_I2C_SDA") (class "Default")
      (node (ref "IC8") (pin "J7") (pinfunction "IO,_DIFFIO_L21p_J7") (pintype "bidirectional"))
    )
    (net (code "125") (name "/FPGA_LED1_G") (class "Default")
      (node (ref "IC8") (pin "D2") (pinfunction "IO,_DIFFIO_L8p,_(DQ2L)/(DQ1L)/(DQ1L)_D2") (pintype "bidirectional"))
    )
    (net (code "126") (name "/FPGA_LED1_R") (class "Default")
      (node (ref "IC8") (pin "E3") (pinfunction "IO,_DIFFIO_L4n,_(DQ2L)/(DQ1L)/(DQ1L)_E3") (pintype "bidirectional"))
    )
    (net (code "127") (name "/FPGA_LED2_G") (class "Default")
      (node (ref "IC8") (pin "J4") (pinfunction "IO,_(DQS0L/CQ1L,DPCLK0)/(DQS0L/CQ1L,DPCLK0)/(DQS0L/CQ1L,DPCLK0)_J4") (pintype "bidirectional"))
    )
    (net (code "128") (name "/FPGA_LED2_R") (class "Default")
      (node (ref "IC8") (pin "E1") (pinfunction "IO,_DIFFIO_L10n,_(_)/(DQ1L)/(DQ1L)_E1") (pintype "bidirectional"))
    )
    (net (code "129") (name "/FPGA_SPI1_ADF_SS") (class "Default")
      (node (ref "IC8") (pin "J5") (pinfunction "IO,_DIFFIO_L18n_J5") (pintype "bidirectional"))
    )
    (net (code "130") (name "/FPGA_SPI1_DAC_SS") (class "Default")
      (node (ref "IC8") (pin "J3") (pinfunction "IO,_VREFB1N3_J3") (pintype "bidirectional"))
    )
    (net (code "131") (name "/FPGA_SPI1_MOSI") (class "Default")
      (node (ref "IC8") (pin "L8") (pinfunction "IO,_DIFFIO_L20p_L8") (pintype "bidirectional"))
    )
    (net (code "132") (name "/FPGA_SPI1_SCLK") (class "Default")
      (node (ref "IC8") (pin "K8") (pinfunction "IO,_DIFFIO_L20n_K8") (pintype "bidirectional"))
    )
    (net (code "133") (name "/FPGA_UART_RX") (class "Default")
      (node (ref "IC8") (pin "J1") (pinfunction "IO,_DIFFIO_L24n,_(DQ0L)/(DQ1L)/(DQ1L)_J1") (pintype "bidirectional"))
    )
    (net (code "134") (name "/FPGA_UART_TX") (class "Default")
      (node (ref "IC8") (pin "J8") (pinfunction "IO,_DIFFIO_L14n_J8") (pintype "bidirectional"))
    )
    (net (code "135") (name "/FX3_CTL0") (class "Default")
      (node (ref "IC8") (pin "L6") (pinfunction "IO,_DIFFIO_L26p,_(DQ0L)/(DQ1L)/(DQ1L)_L6") (pintype "bidirectional"))
    )
    (net (code "136") (name "/FX3_CTL1") (class "Default")
      (node (ref "IC8") (pin "L7") (pinfunction "IO,_DIFFIO_L30n_L7") (pintype "bidirectional"))
    )
    (net (code "137") (name "/FX3_CTL2") (class "Default")
      (node (ref "IC8") (pin "M1") (pinfunction "IO,_DIFFIO_L27n,_(_)/(DQ1L)/(DQ1L)_M1") (pintype "bidirectional"))
    )
    (net (code "138") (name "/FX3_CTL3") (class "Default")
      (node (ref "IC8") (pin "M2") (pinfunction "IO,_DIFFIO_L27p,_(DQ0L)/(DQ1L)/(DQ1L)_M2") (pintype "bidirectional"))
    )
    (net (code "139") (name "/FX3_CTL4") (class "Default")
      (node (ref "IC8") (pin "M3") (pinfunction "IO,_DIFFIO_L28n,_(DQ1L)/(DQ3L)/(DQ1L)_M3") (pintype "bidirectional"))
    )
    (net (code "140") (name "/FX3_CTL5") (class "Default")
      (node (ref "IC8") (pin "M4") (pinfunction "IO,_DIFFIO_L28p,_(DM0L)/(DM1L/BWS#1L)/(DM1L/BWS#1L)_M4") (pintype "bidirectional"))
    )
    (net (code "141") (name "/FX3_CTL6") (class "Default")
      (node (ref "IC8") (pin "M6") (pinfunction "IO,_DIFFIO_L26n,_(DQ0L)/(DQ1L)/(DQ1L)_M6") (pintype "bidirectional"))
    )
    (net (code "142") (name "/FX3_CTL7") (class "Default")
      (node (ref "IC8") (pin "M7") (pinfunction "IO,_DIFFIO_L41n_M7") (pintype "bidirectional"))
    )
    (net (code "143") (name "/FX3_CTL8") (class "Default")
      (node (ref "IC8") (pin "M8") (pinfunction "IO,_DIFFIO_L42p_M8") (pintype "bidirectional"))
    )
    (net (code "144") (name "/FX3_CTL9") (class "Default")
      (node (ref "IC8") (pin "N1") (pinfunction "IO,_DIFFIO_L29n,_(DQ1L)/(DQ3L)/(DQ1L)_N1") (pintype "bidirectional"))
    )
    (net (code "145") (name "/FX3_CTL10") (class "Default")
      (node (ref "IC8") (pin "N2") (pinfunction "IO,_DIFFIO_L29p,_(DQ1L)/(DQ3L)/(DQ1L)_N2") (pintype "bidirectional"))
    )
    (net (code "146") (name "/FX3_CTL11") (class "Default")
      (node (ref "IC8") (pin "N5") (pinfunction "IO,_(DQ1L)/(DQ3L)/(DQ1L)_N5") (pintype "bidirectional"))
    )
    (net (code "147") (name "/FX3_CTL12") (class "Default")
      (node (ref "IC8") (pin "N6") (pinfunction "IO,_DIFFIO_L41p,_(DQ3L)/(DQ3L)/(DQ1L)_N6") (pintype "bidirectional"))
    )
    (net (code "148") (name "/FX3_CTL13") (class "Default")
      (node (ref "IC8") (pin "P2") (pinfunction "IO,_DIFFIO_L32p,_(DQ1L)/(DQ3L)/(DQ1L)_P2") (pintype "bidirectional"))
    )
    (net (code "149") (name "/FX3_CTL14") (class "Default")
      (node (ref "IC8") (pin "N7") (pinfunction "IO,_DIFFIO_L49p_N7") (pintype "bidirectional"))
    )
    (net (code "151") (name "/FX3_LED_G") (class "Default")
      (node (ref "IC8") (pin "G5") (pinfunction "IO,_VREFB1N0_G5") (pintype "bidirectional"))
    )
    (net (code "152") (name "/FX3_LED_R") (class "Default")
      (node (ref "IC8") (pin "H5") (pinfunction "IO,_VREFB1N2_H5") (pintype "bidirectional"))
    )
    (net (code "153") (name "/LM75_OS") (class "Default")
      (node (ref "IC8") (pin "J6") (pinfunction "IO,_DIFFIO_L9n,_(DQ2L)/(DQ1L)/(DQ1L)_J6") (pintype "bidirectional"))
    )
    (net (code "154") (name "/VCC1P8") (class "Default")
      (node (ref "R46") (pin "2") (pinfunction "2_2") (pintype "passive"))
    )
    (net (code "155") (name "GND") (class "Default")
      (node (ref "C103") (pin "2") (pinfunction "2_2") (pintype "passive"))
      (node (ref "C104") (pin "2") (pinfunction "2_2") (pintype "passive"))
      (node (ref "C105") (pin "2") (pinfunction "2_2") (pintype "passive"))
      (node (ref "C106") (pin "2") (pinfunction "2_2") (pintype "passive"))
      (node (ref "C107") (pin "2") (pinfunction "2_2") (pintype "passive"))
      (node (ref "C108") (pin "2") (pinfunction "2_2") (pintype "passive"))
      (node (ref "C109") (pin "2") (pinfunction "2_2") (pintype "passive"))
      (node (ref "C110") (pin "2") (pinfunction "2_2") (pintype "passive"))
      (node (ref "C111") (pin "2") (pinfunction "2_2") (pintype "passive"))
      (node (ref "C112") (pin "2") (pinfunction "2_2") (pintype "passive"))
      (node (ref "C113") (pin "2") (pinfunction "2_2") (pintype "passive"))
      (node (ref "C114") (pin "2") (pinfunction "2_2") (pintype "passive"))
      (node (ref "R42") (pin "2") (pinfunction "2_2") (pintype "passive"))
      (node (ref "R43") (pin "2") (pinfunction "2_2") (pintype "passive"))
      (node (ref "R44") (pin "2") (pinfunction "2_2") (pintype "passive"))
      (node (ref "R45") (pin "2") (pinfunction "2_2") (pintype "passive"))
      (node (ref "R47") (pin "1") (pinfunction "1_1") (pintype "passive"))
    )
    (net (code "156") (name "Net-(IC8D-IO,_RDN2)") (class "Default")
      (node (ref "IC8") (pin "AB19") (pinfunction "IO,_RDN2_AB19") (pintype "bidirectional"))
      (node (ref "R47") (pin "2") (pinfunction "2_2") (pintype "passive"))
    )
    (net (code "157") (name "Net-(IC8D-IO,_RUP2)") (class "Default")
      (node (ref "IC8") (pin "AA19") (pinfunction "IO,_RUP2_AA19") (pintype "bidirectional"))
      (node (ref "R46") (pin "1") (pinfunction "1_1") (pintype "passive"))
    )
    (net (code "158") (name "VREF_DDR2") (class "Default")
      (node (ref "C103") (pin "1") (pinfunction "1_1") (pintype "passive"))
      (node (ref "C104") (pin "1") (pinfunction "1_1") (pintype "passive"))
      (node (ref "C105") (pin "1") (pinfunction "1_1") (pintype "passive"))
      (node (ref "C106") (pin "1") (pinfunction "1_1") (pintype "passive"))
      (node (ref "C107") (pin "1") (pinfunction "1_1") (pintype "passive"))
      (node (ref "C108") (pin "1") (pinfunction "1_1") (pintype "passive"))
      (node (ref "C109") (pin "1") (pinfunction "1_1") (pintype "passive"))
      (node (ref "C110") (pin "1") (pinfunction "1_1") (pintype "passive"))
      (node (ref "C111") (pin "1") (pinfunction "1_1") (pintype "passive"))
      (node (ref "C112") (pin "1") (pinfunction "1_1") (pintype "passive"))
      (node (ref "C113") (pin "1") (pinfunction "1_1") (pintype "passive"))
      (node (ref "C114") (pin "1") (pinfunction "1_1") (pintype "passive"))
      (node (ref "IC8") (pin "AA18") (pinfunction "IO,_VREFB4N1_AA18") (pintype "bidirectional"))
      (node (ref "IC8") (pin "AB4") (pinfunction "IO,_VREFB3N2_AB4") (pintype "bidirectional"))
      (node (ref "IC8") (pin "M5") (pinfunction "IO,_VREFB2N0_M5") (pintype "bidirectional"))
      (node (ref "IC8") (pin "P5") (pinfunction "IO,_VREFB2N1_P5") (pintype "bidirectional"))
      (node (ref "IC8") (pin "R5") (pinfunction "IO,_VREFB2N3_R5") (pintype "bidirectional"))
      (node (ref "IC8") (pin "T3") (pinfunction "IO,_VREFB2N2_T3") (pintype "bidirectional"))
      (node (ref "IC8") (pin "U11") (pinfunction "IO,_VREFB3N0_U11") (pintype "bidirectional"))
      (node (ref "IC8") (pin "V12") (pinfunction "IO,_VREFB4N3_V12") (pintype "bidirectional"))
      (node (ref "IC8") (pin "V16") (pinfunction "IO,_VREFB4N0_V16") (pintype "bidirectional"))
      (node (ref "IC8") (pin "V9") (pinfunction "IO,_VREFB3N1_V9") (pintype "bidirectional"))
      (node (ref "IC8") (pin "W14") (pinfunction "IO,_VREFB4N2_W14") (pintype "bidirectional"))
      (node (ref "IC8") (pin "Y4") (pinfunction "IO,_VREFB3N3_Y4") (pintype "bidirectional"))
    )
    (net (code "159") (name "unconnected-(IC8B-IO,_DIFFIO_L34n,_(DQ1L){slash}(DQ3L){slash}(DQ1L)-PadP3)") (class "Default")
      (node (ref "IC8") (pin "P3") (pinfunction "IO,_DIFFIO_L34n,_(DQ1L)/(DQ3L)/(DQ1L)_P3") (pintype "bidirectional+no_connect"))
    )
    (net (code "160") (name "unconnected-(IC8B-IO,_DIFFIO_L34p,_(DQS1L{slash}CQ1L#,DPCLK1){slash}(DQS1L{slash}CQ1L#,DPCLK1){slash}(DQS1L{slash}CQ1L#,DPCLK1)-PadP4)") (class "Default")
      (node (ref "IC8") (pin "P4") (pinfunction "IO,_DIFFIO_L34p,_(DQS1L/CQ1L#,DPCLK1)/(DQS1L/CQ1L#,DPCLK1)/(DQS1L/CQ1L#,DPCLK1)_P4") (pintype "bidirectional+no_connect"))
    )
  )
)
